# FlameClock_1_1_sh2.net
KiCad netlist of a schematic drawn in Altium Designer
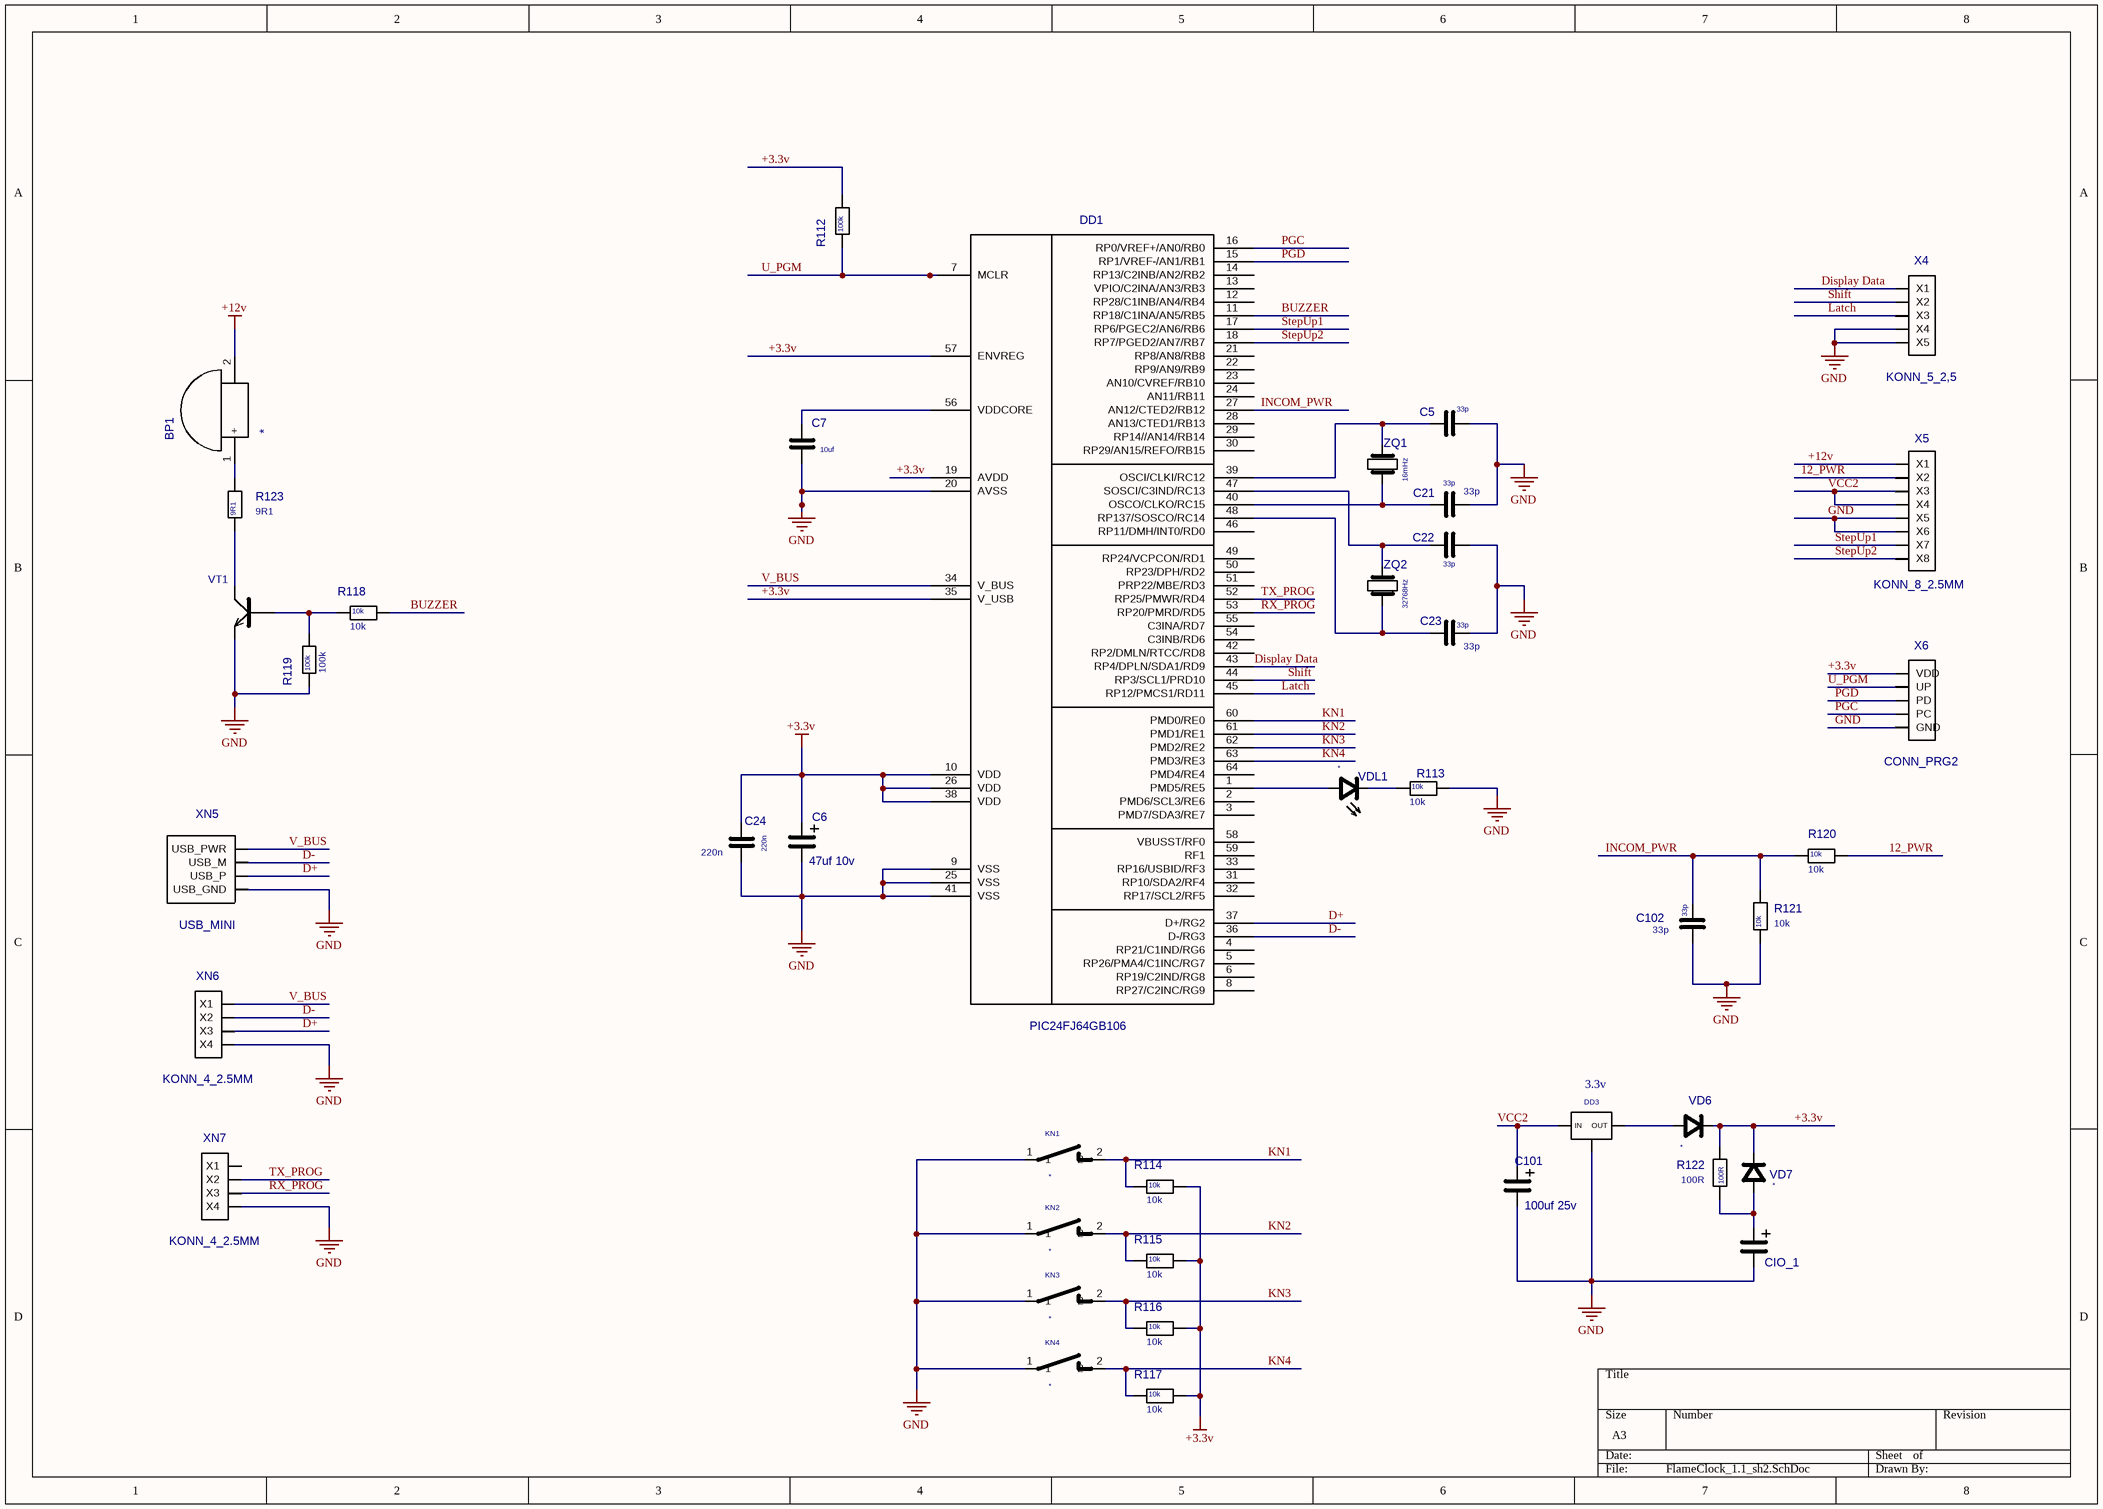
[diagram p0: FlameClock_1.1_sh2.SchDoc]

(export (version "E")
  (design (tool "Eeschema 10.0.6"))
  (components
    (comp (ref "BP1") (value "*") (footprint "ZIPPER") (libsource (lib "MyALib_Def") (part "Buzzer")))
    (comp (ref "C5") (value "33p") (footprint "CC0805_S") (libsource (lib "MyALib_Def") (part "C0805_S")))
    (comp (ref "C6")
      (value "47uf 10v")
      (footprint "CC0805_C_TANTAL_POLAR")
      (libsource (lib "MyALib_Def") (part "C0805_C_TAN_POLAR"))
    )
    (comp (ref "C7") (value "10uf") (footprint "CC0805_B") (libsource (lib "MyALib_Def") (part "C0805_B")))
    (comp (ref "C21")
      (value "33p")
      (footprint "CC0805_S")
      (fields (field (name "ALTIUM_VALUE") "33p"))
      (libsource (lib "MyALib_Def") (part "C0805_S"))
    )
    (comp (ref "C22") (value "33p") (footprint "CC0805_S") (libsource (lib "MyALib_Def") (part "C0805_S")))
    (comp (ref "C23")
      (value "33p")
      (footprint "CC0805_S")
      (fields (field (name "ALTIUM_VALUE") "33p"))
      (libsource (lib "MyALib_Def") (part "C0805_S"))
    )
    (comp (ref "C24")
      (value "220n")
      (footprint "CC0805_S")
      (fields (field (name "ALTIUM_VALUE") "220n"))
      (libsource (lib "my_lib_def") (part "C0805_S"))
    )
    (comp (ref "C101")
      (value "100uf 25v")
      (footprint "CE2.5")
      (libsource (lib "MyALib_Def") (part "CE2.5_5MM"))
    )
    (comp (ref "C102")
      (value "33p")
      (footprint "CC0805_S")
      (fields (field (name "ALTIUM_VALUE") "33p"))
      (libsource (lib "MyALib_Def") (part "C0805_S"))
    )
    (comp (ref "CIO_1") (value "*") (footprint "CE10") (libsource (lib "MyALib_Def") (part "CE5.0_10MM")))
    (comp (ref "DD1")
      (value "PIC24FJ64GB106")
      (footprint "TQFP-64")
      (libsource (lib "my_lib_mikroshem") (part "PIC24FJ64GB106"))
    )
    (comp (ref "DD3")
      (value "3.3v")
      (footprint "SOT223")
      (fields (field (name "Comment") "LD1117S"))
      (libsource (lib "MyALib_Microshem") (part "LD1117S"))
    )
    (comp (ref "KN1") (value "*") (footprint "KNOP_12X12") (libsource (lib "MyALib_Def") (part "KNOP_12X12")))
    (comp (ref "KN2") (value "*") (footprint "KNOP_12X12") (libsource (lib "MyALib_Def") (part "KNOP_12X12")))
    (comp (ref "KN3") (value "*") (footprint "KNOP_12X12") (libsource (lib "MyALib_Def") (part "KNOP_12X12")))
    (comp (ref "KN4") (value "*") (footprint "KNOP_12X12") (libsource (lib "MyALib_Def") (part "KNOP_12X12")))
    (comp (ref "R112") (value "100k") (footprint "R0805_S") (libsource (lib "MyALib_Def") (part "R0805_S")))
    (comp (ref "R113")
      (value "10k")
      (footprint "R0805_S")
      (fields (field (name "ALTIUM_VALUE") "10k"))
      (libsource (lib "MyALib_Def") (part "R0805_S"))
    )
    (comp (ref "R114")
      (value "10k")
      (footprint "R0805_S")
      (fields (field (name "ALTIUM_VALUE") "10k"))
      (libsource (lib "MyALib_Def") (part "R0805_S"))
    )
    (comp (ref "R115")
      (value "10k")
      (footprint "R0805_S")
      (fields (field (name "ALTIUM_VALUE") "10k"))
      (libsource (lib "MyALib_Def") (part "R0805_S"))
    )
    (comp (ref "R116")
      (value "10k")
      (footprint "R0805_S")
      (fields (field (name "ALTIUM_VALUE") "10k"))
      (libsource (lib "MyALib_Def") (part "R0805_S"))
    )
    (comp (ref "R117")
      (value "10k")
      (footprint "R0805_S")
      (fields (field (name "ALTIUM_VALUE") "10k"))
      (libsource (lib "MyALib_Def") (part "R0805_S"))
    )
    (comp (ref "R118")
      (value "10k")
      (footprint "R0805_S")
      (fields (field (name "ALTIUM_VALUE") "10k"))
      (libsource (lib "MyALib_Def") (part "R0805_S"))
    )
    (comp (ref "R119")
      (value "100k")
      (footprint "R0805_S")
      (fields (field (name "ALTIUM_VALUE") "100k"))
      (libsource (lib "MyALib_Def") (part "R0805_S"))
    )
    (comp (ref "R120")
      (value "10k")
      (footprint "R0805_S")
      (fields (field (name "ALTIUM_VALUE") "10k"))
      (libsource (lib "MyALib_Def") (part "R0805_S"))
    )
    (comp (ref "R121")
      (value "10k")
      (footprint "R0805_S")
      (fields (field (name "ALTIUM_VALUE") "10k"))
      (libsource (lib "MyALib_Def") (part "R0805_S"))
    )
    (comp (ref "R122")
      (value "100R")
      (footprint "R0805_S")
      (fields (field (name "ALTIUM_VALUE") "100R"))
      (libsource (lib "MyALib_Def") (part "R0805_S"))
    )
    (comp (ref "R123")
      (value "9R1")
      (footprint "R0805_S")
      (fields (field (name "ALTIUM_VALUE") "9R1"))
      (libsource (lib "MyALib_Def") (part "R0805_S"))
    )
    (comp (ref "VD6")
      (value "*")
      (footprint "DIOD_SOD123")
      (libsource (lib "MyALib_Def") (part "DIODE_SOD123"))
    )
    (comp (ref "VD7")
      (value "*")
      (footprint "DIOD_SOD123")
      (libsource (lib "MyALib_Def") (part "DIODE_SOD123"))
    )
    (comp (ref "VDL1") (value "*") (footprint "LED0805") (libsource (lib "MyALib_Def") (part "L_DIODE0805")))
    (comp (ref "VT1") (value "*") (footprint "SOT-23") (libsource (lib "MyALib_Def") (part "NPN_SOT23")))
    (comp (ref "X4")
      (value "KONN_5_2,5")
      (footprint "KONN_5_2.5MM")
      (libsource (lib "MyALib_Konnect") (part "KONN_5_2,5"))
    )
    (comp (ref "X5")
      (value "KONN_8_2.5MM")
      (footprint "KONN_8_2.5MM")
      (libsource (lib "MyALib_Konnect") (part "KONN_8_2.5MM"))
    )
    (comp (ref "X6")
      (value "CONN_PRG2")
      (footprint "CONN_PRG2")
      (libsource (lib "MyALib_Konnect") (part "CONN_PRG2"))
    )
    (comp (ref "XN5")
      (value "USB_MINI")
      (footprint "USB_MINI")
      (libsource (lib "MyALib_Konnect") (part "USB_MINI"))
    )
    (comp (ref "XN6")
      (value "KONN_4_2.5MM")
      (footprint "KONN_4_2.5MM")
      (libsource (lib "MyALib_Konnect") (part "KONN_4_2.5MM"))
    )
    (comp (ref "XN7")
      (value "KONN_4_2.5MM")
      (footprint "KONN_4_2.5MM")
      (libsource (lib "MyALib_Konnect") (part "KONN_4_2.5MM"))
    )
    (comp (ref "ZQ1") (value "16mHz") (footprint "ZQ") (libsource (lib "MyALib_Def") (part "ZQ")))
    (comp (ref "ZQ2")
      (value "32768Hz")
      (footprint "ZQ_CLOCK")
      (libsource (lib "MyALib_Def") (part "ZQ_CLOCK"))
    )
  )
  (nets
    (net (code "1") (name "+3.3v") (class "Default")
      (node (ref "C24") (pin "1") (pinfunction "1_1") (pintype "passive"))
      (node (ref "C6") (pin "2") (pinfunction "pl_2") (pintype "passive"))
      (node (ref "DD1") (pin "10") (pinfunction "VDD_10") (pintype "passive"))
      (node (ref "DD1") (pin "19") (pinfunction "AVDD_19") (pintype "passive"))
      (node (ref "DD1") (pin "26") (pinfunction "VDD_26") (pintype "passive"))
      (node (ref "DD1") (pin "35") (pinfunction "V_USB_35") (pintype "passive"))
      (node (ref "DD1") (pin "38") (pinfunction "VDD_38") (pintype "passive"))
      (node (ref "DD1") (pin "57") (pinfunction "ENVREG_57") (pintype "passive"))
      (node (ref "R112") (pin "1") (pinfunction "1_1") (pintype "passive"))
      (node (ref "R114") (pin "1") (pinfunction "1_1") (pintype "passive"))
      (node (ref "R115") (pin "1") (pinfunction "1_1") (pintype "passive"))
      (node (ref "R116") (pin "1") (pinfunction "1_1") (pintype "passive"))
      (node (ref "R117") (pin "1") (pinfunction "1_1") (pintype "passive"))
      (node (ref "R122") (pin "1") (pinfunction "1_1") (pintype "passive"))
      (node (ref "VD6") (pin "1") (pinfunction "k_1") (pintype "passive"))
      (node (ref "VD7") (pin "1") (pinfunction "k_1") (pintype "passive"))
      (node (ref "X6") (pin "1") (pinfunction "VDD_1") (pintype "passive"))
    )
    (net (code "2") (name "+12v") (class "Default")
      (node (ref "BP1") (pin "2") (pinfunction "-_2") (pintype "passive"))
      (node (ref "X5") (pin "1") (pinfunction "X1_1") (pintype "passive"))
    )
    (net (code "3") (name "/12_PWR") (class "Default")
      (node (ref "R120") (pin "1") (pinfunction "1_1") (pintype "passive"))
      (node (ref "X5") (pin "2") (pinfunction "X2_2") (pintype "passive"))
    )
    (net (code "4") (name "/BUZZER") (class "Default")
      (node (ref "DD1") (pin "11") (pinfunction "RP18/C1INA/AN5/RB5_11") (pintype "passive"))
      (node (ref "R118") (pin "1") (pinfunction "1_1") (pintype "passive"))
    )
    (net (code "5") (name "/D+") (class "Default")
      (node (ref "DD1") (pin "37") (pinfunction "D+/RG2_37") (pintype "passive"))
      (node (ref "XN5") (pin "3") (pinfunction "USB_P_3") (pintype "passive"))
      (node (ref "XN6") (pin "3") (pinfunction "X3_3") (pintype "passive"))
    )
    (net (code "6") (name "/D-") (class "Default")
      (node (ref "DD1") (pin "36") (pinfunction "D-/RG3_36") (pintype "passive"))
      (node (ref "XN5") (pin "2") (pinfunction "USB_M_2") (pintype "passive"))
      (node (ref "XN6") (pin "2") (pinfunction "X2_2") (pintype "passive"))
    )
    (net (code "7") (name "/Display Data") (class "Default")
      (node (ref "DD1") (pin "43") (pinfunction "RP4/DPLN/SDA1/RD9_43") (pintype "passive"))
      (node (ref "X4") (pin "1") (pinfunction "X1_1") (pintype "passive"))
    )
    (net (code "8") (name "/INCOM_PWR") (class "Default")
      (node (ref "C102") (pin "2") (pinfunction "2_2") (pintype "passive"))
      (node (ref "DD1") (pin "27") (pinfunction "AN12/CTED2/RB12_27") (pintype "passive"))
      (node (ref "R120") (pin "2") (pinfunction "2_2") (pintype "passive"))
      (node (ref "R121") (pin "1") (pinfunction "1_1") (pintype "passive"))
    )
    (net (code "9") (name "/KN1") (class "Default")
      (node (ref "DD1") (pin "60") (pinfunction "PMD0/RE0_60") (pintype "passive"))
      (node (ref "KN1") (pin "2") (pinfunction "2_2") (pintype "passive"))
      (node (ref "R114") (pin "2") (pinfunction "2_2") (pintype "passive"))
    )
    (net (code "10") (name "/KN2") (class "Default")
      (node (ref "DD1") (pin "61") (pinfunction "PMD1/RE1_61") (pintype "passive"))
      (node (ref "KN2") (pin "2") (pinfunction "2_2") (pintype "passive"))
      (node (ref "R115") (pin "2") (pinfunction "2_2") (pintype "passive"))
    )
    (net (code "11") (name "/KN3") (class "Default")
      (node (ref "DD1") (pin "62") (pinfunction "PMD2/RE2_62") (pintype "passive"))
      (node (ref "KN3") (pin "2") (pinfunction "2_2") (pintype "passive"))
      (node (ref "R116") (pin "2") (pinfunction "2_2") (pintype "passive"))
    )
    (net (code "12") (name "/KN4") (class "Default")
      (node (ref "DD1") (pin "63") (pinfunction "PMD3/RE3_63") (pintype "passive"))
      (node (ref "KN4") (pin "2") (pinfunction "2_2") (pintype "passive"))
      (node (ref "R117") (pin "2") (pinfunction "2_2") (pintype "passive"))
    )
    (net (code "13") (name "/Latch") (class "Default")
      (node (ref "DD1") (pin "45") (pinfunction "RP12/PMCS1/RD11_45") (pintype "passive"))
      (node (ref "X4") (pin "3") (pinfunction "X3_3") (pintype "passive"))
    )
    (net (code "14") (name "/PGC") (class "Default")
      (node (ref "DD1") (pin "16") (pinfunction "RP0/VREF+/AN0/RB0_16") (pintype "passive"))
      (node (ref "X6") (pin "4") (pinfunction "PC_4") (pintype "passive"))
    )
    (net (code "15") (name "/PGD") (class "Default")
      (node (ref "DD1") (pin "15") (pinfunction "RP1/VREF-/AN1/RB1_15") (pintype "passive"))
      (node (ref "X6") (pin "3") (pinfunction "PD_3") (pintype "passive"))
    )
    (net (code "16") (name "/RX_PROG") (class "Default")
      (node (ref "DD1") (pin "53") (pinfunction "RP20/PMRD/RD5_53") (pintype "passive"))
      (node (ref "XN7") (pin "3") (pinfunction "X3_3") (pintype "passive"))
    )
    (net (code "17") (name "/Shift") (class "Default")
      (node (ref "DD1") (pin "44") (pinfunction "RP3/SCL1/PRD10_44") (pintype "passive"))
      (node (ref "X4") (pin "2") (pinfunction "X2_2") (pintype "passive"))
    )
    (net (code "18") (name "/StepUp1") (class "Default")
      (node (ref "DD1") (pin "17") (pinfunction "RP6/PGEC2/AN6/RB6_17") (pintype "passive"))
      (node (ref "X5") (pin "7") (pinfunction "X7_7") (pintype "passive"))
    )
    (net (code "19") (name "/StepUp2") (class "Default")
      (node (ref "DD1") (pin "18") (pinfunction "RP7/PGED2/AN7/RB7_18") (pintype "passive"))
      (node (ref "X5") (pin "8") (pinfunction "X8_8") (pintype "passive"))
    )
    (net (code "20") (name "/TX_PROG") (class "Default")
      (node (ref "DD1") (pin "52") (pinfunction "RP25/PMWR/RD4_52") (pintype "passive"))
      (node (ref "XN7") (pin "2") (pinfunction "X2_2") (pintype "passive"))
    )
    (net (code "21") (name "/U_PGM") (class "Default")
      (node (ref "DD1") (pin "7") (pinfunction "MCLR_7") (pintype "passive"))
      (node (ref "R112") (pin "2") (pinfunction "2_2") (pintype "passive"))
      (node (ref "X6") (pin "2") (pinfunction "UP_2") (pintype "passive"))
    )
    (net (code "22") (name "/VCC2") (class "Default")
      (node (ref "C101") (pin "1") (pinfunction "1_1") (pintype "passive"))
      (node (ref "DD3") (pin "1") (pinfunction "IN_1") (pintype "passive"))
      (node (ref "X5") (pin "3") (pinfunction "X3_3") (pintype "passive"))
      (node (ref "X5") (pin "4") (pinfunction "X4_4") (pintype "passive"))
    )
    (net (code "23") (name "/V_BUS") (class "Default")
      (node (ref "DD1") (pin "34") (pinfunction "V_BUS_34") (pintype "passive"))
      (node (ref "XN5") (pin "1") (pinfunction "USB_PWR_1") (pintype "passive"))
      (node (ref "XN6") (pin "1") (pinfunction "X1_1") (pintype "passive"))
    )
    (net (code "24") (name "GND") (class "Default")
      (node (ref "C101") (pin "2") (pinfunction "2_2") (pintype "passive"))
      (node (ref "C102") (pin "1") (pinfunction "1_1") (pintype "passive"))
      (node (ref "C21") (pin "2") (pinfunction "2_2") (pintype "passive"))
      (node (ref "C22") (pin "2") (pinfunction "2_2") (pintype "passive"))
      (node (ref "C23") (pin "2") (pinfunction "2_2") (pintype "passive"))
      (node (ref "C24") (pin "2") (pinfunction "2_2") (pintype "passive"))
      (node (ref "C5") (pin "2") (pinfunction "2_2") (pintype "passive"))
      (node (ref "C6") (pin "1") (pinfunction "min_1") (pintype "passive"))
      (node (ref "C7") (pin "2") (pinfunction "2_2") (pintype "passive"))
      (node (ref "CIO_1") (pin "2") (pinfunction "min_2") (pintype "passive"))
      (node (ref "DD1") (pin "20") (pinfunction "AVSS_20") (pintype "passive"))
      (node (ref "DD1") (pin "25") (pinfunction "VSS_25") (pintype "passive"))
      (node (ref "DD1") (pin "41") (pinfunction "VSS_41") (pintype "passive"))
      (node (ref "DD1") (pin "9") (pinfunction "VSS_9") (pintype "passive"))
      (node (ref "DD3") (pin "3") (pinfunction "GND_3") (pintype "passive"))
      (node (ref "KN1") (pin "1") (pinfunction "1_1") (pintype "passive"))
      (node (ref "KN2") (pin "1") (pinfunction "1_1") (pintype "passive"))
      (node (ref "KN3") (pin "1") (pinfunction "1_1") (pintype "passive"))
      (node (ref "KN4") (pin "1") (pinfunction "1_1") (pintype "passive"))
      (node (ref "R113") (pin "1") (pinfunction "1_1") (pintype "passive"))
      (node (ref "R119") (pin "2") (pinfunction "2_2") (pintype "passive"))
      (node (ref "R121") (pin "2") (pinfunction "2_2") (pintype "passive"))
      (node (ref "VT1") (pin "3") (pinfunction "e_3") (pintype "passive"))
      (node (ref "X4") (pin "4") (pinfunction "X4_4") (pintype "passive"))
      (node (ref "X4") (pin "5") (pinfunction "X5_5") (pintype "passive"))
      (node (ref "X5") (pin "5") (pinfunction "X5_5") (pintype "passive"))
      (node (ref "X5") (pin "6") (pinfunction "X6_6") (pintype "passive"))
      (node (ref "X6") (pin "5") (pinfunction "GND_5") (pintype "passive"))
      (node (ref "XN5") (pin "5") (pinfunction "USB_GND_5") (pintype "passive"))
      (node (ref "XN6") (pin "4") (pinfunction "X4_4") (pintype "passive"))
      (node (ref "XN7") (pin "4") (pinfunction "X4_4") (pintype "passive"))
    )
    (net (code "25") (name "Net-(BP1-+)") (class "Default")
      (node (ref "BP1") (pin "1") (pinfunction "+_1") (pintype "passive"))
      (node (ref "R123") (pin "1") (pinfunction "1_1") (pintype "passive"))
    )
    (net (code "26") (name "Net-(CIO_1-pl)") (class "Default")
      (node (ref "CIO_1") (pin "1") (pinfunction "pl_1") (pintype "passive"))
      (node (ref "R122") (pin "2") (pinfunction "2_2") (pintype "passive"))
      (node (ref "VD7") (pin "2") (pinfunction "a_2") (pintype "passive"))
    )
    (net (code "27") (name "Net-(DD1-OSCI{slash}CLKI{slash}RC12)") (class "Default")
      (node (ref "C5") (pin "1") (pinfunction "1_1") (pintype "passive"))
      (node (ref "DD1") (pin "39") (pinfunction "OSCI/CLKI/RC12_39") (pintype "passive"))
      (node (ref "ZQ1") (pin "1") (pinfunction "1_1") (pintype "passive"))
    )
    (net (code "28") (name "Net-(DD1-OSCO{slash}CLKO{slash}RC15)") (class "Default")
      (node (ref "C21") (pin "1") (pinfunction "1_1") (pintype "passive"))
      (node (ref "DD1") (pin "40") (pinfunction "OSCO/CLKO/RC15_40") (pintype "passive"))
      (node (ref "ZQ1") (pin "2") (pinfunction "2_2") (pintype "passive"))
    )
    (net (code "29") (name "Net-(DD1-PMD5{slash}RE5)") (class "Default")
      (node (ref "DD1") (pin "1") (pinfunction "PMD5/RE5_1") (pintype "passive"))
      (node (ref "VDL1") (pin "2") (pinfunction "2_2") (pintype "passive"))
    )
    (net (code "30") (name "Net-(DD1-RP137{slash}SOSCO{slash}RC14)") (class "Default")
      (node (ref "C23") (pin "1") (pinfunction "1_1") (pintype "passive"))
      (node (ref "DD1") (pin "48") (pinfunction "RP137/SOSCO/RC14_48") (pintype "passive"))
      (node (ref "ZQ2") (pin "2") (pinfunction "2_2") (pintype "passive"))
    )
    (net (code "31") (name "Net-(DD1-SOSCI{slash}C3IND{slash}RC13)") (class "Default")
      (node (ref "C22") (pin "1") (pinfunction "1_1") (pintype "passive"))
      (node (ref "DD1") (pin "47") (pinfunction "SOSCI/C3IND/RC13_47") (pintype "passive"))
      (node (ref "ZQ2") (pin "1") (pinfunction "1_1") (pintype "passive"))
    )
    (net (code "32") (name "Net-(DD1-VDDCORE)") (class "Default")
      (node (ref "C7") (pin "1") (pinfunction "1_1") (pintype "passive"))
      (node (ref "DD1") (pin "56") (pinfunction "VDDCORE_56") (pintype "passive"))
    )
    (net (code "33") (name "Net-(DD3-OUT)") (class "Default")
      (node (ref "DD3") (pin "2") (pinfunction "OUT_2") (pintype "passive"))
      (node (ref "VD6") (pin "2") (pinfunction "a_2") (pintype "passive"))
    )
    (net (code "34") (name "Net-(R113-Pad2)") (class "Default")
      (node (ref "R113") (pin "2") (pinfunction "2_2") (pintype "passive"))
      (node (ref "VDL1") (pin "1") (pinfunction "1_1") (pintype "passive"))
    )
    (net (code "35") (name "Net-(VT1-b)") (class "Default")
      (node (ref "R118") (pin "2") (pinfunction "2_2") (pintype "passive"))
      (node (ref "R119") (pin "1") (pinfunction "1_1") (pintype "passive"))
      (node (ref "VT1") (pin "1") (pinfunction "b_1") (pintype "passive"))
    )
    (net (code "36") (name "Net-(VT1-k)") (class "Default")
      (node (ref "R123") (pin "2") (pinfunction "2_2") (pintype "passive"))
      (node (ref "VT1") (pin "2") (pinfunction "k_2") (pintype "passive"))
    )
    (net (code "37") (name "unconnected-(DD1-AN10{slash}CVREF{slash}RB10-Pad23)") (class "Default")
      (node (ref "DD1") (pin "23") (pinfunction "AN10/CVREF/RB10_23") (pintype "passive"))
    )
    (net (code "38") (name "unconnected-(DD1-AN11{slash}RB11-Pad24)") (class "Default")
      (node (ref "DD1") (pin "24") (pinfunction "AN11/RB11_24") (pintype "passive"))
    )
    (net (code "39") (name "unconnected-(DD1-AN13{slash}CTED1{slash}RB13-Pad28)") (class "Default")
      (node (ref "DD1") (pin "28") (pinfunction "AN13/CTED1/RB13_28") (pintype "passive"))
    )
    (net (code "40") (name "unconnected-(DD1-C3INA{slash}RD7-Pad55)") (class "Default")
      (node (ref "DD1") (pin "55") (pinfunction "C3INA/RD7_55") (pintype "passive"))
    )
    (net (code "41") (name "unconnected-(DD1-C3INB{slash}RD6-Pad54)") (class "Default")
      (node (ref "DD1") (pin "54") (pinfunction "C3INB/RD6_54") (pintype "passive"))
    )
    (net (code "42") (name "unconnected-(DD1-PMD4{slash}RE4-Pad64)") (class "Default")
      (node (ref "DD1") (pin "64") (pinfunction "PMD4/RE4_64") (pintype "passive"))
    )
    (net (code "43") (name "unconnected-(DD1-PMD6{slash}SCL3{slash}RE6-Pad2)") (class "Default")
      (node (ref "DD1") (pin "2") (pinfunction "PMD6/SCL3/RE6_2") (pintype "passive"))
    )
    (net (code "44") (name "unconnected-(DD1-PMD7{slash}SDA3{slash}RE7-Pad3)") (class "Default")
      (node (ref "DD1") (pin "3") (pinfunction "PMD7/SDA3/RE7_3") (pintype "passive"))
    )
    (net (code "45") (name "unconnected-(DD1-PRP22{slash}MBE{slash}RD3-Pad51)") (class "Default")
      (node (ref "DD1") (pin "51") (pinfunction "PRP22/MBE/RD3_51") (pintype "passive"))
    )
    (net (code "46") (name "unconnected-(DD1-RF1-Pad59)") (class "Default")
      (node (ref "DD1") (pin "59") (pinfunction "RF1_59") (pintype "passive"))
    )
    (net (code "47") (name "unconnected-(DD1-RP2{slash}DMLN{slash}RTCC{slash}RD8-Pad42)") (class "Default")
      (node (ref "DD1") (pin "42") (pinfunction "RP2/DMLN/RTCC/RD8_42") (pintype "passive"))
    )
    (net (code "48") (name "unconnected-(DD1-RP8{slash}AN8{slash}RB8-Pad21)") (class "Default")
      (node (ref "DD1") (pin "21") (pinfunction "RP8/AN8/RB8_21") (pintype "passive"))
    )
    (net (code "49") (name "unconnected-(DD1-RP9{slash}AN9{slash}RB9-Pad22)") (class "Default")
      (node (ref "DD1") (pin "22") (pinfunction "RP9/AN9/RB9_22") (pintype "passive"))
    )
    (net (code "50") (name "unconnected-(DD1-RP10{slash}SDA2{slash}RF4-Pad31)") (class "Default")
      (node (ref "DD1") (pin "31") (pinfunction "RP10/SDA2/RF4_31") (pintype "passive"))
    )
    (net (code "51") (name "unconnected-(DD1-RP11{slash}DMH{slash}INT0{slash}RD0-Pad46)") (class "Default")
      (node (ref "DD1") (pin "46") (pinfunction "RP11/DMH/INT0/RD0_46") (pintype "passive"))
    )
    (net (code "52") (name "unconnected-(DD1-RP13{slash}C2INB{slash}AN2{slash}RB2-Pad14)") (class "Default")
      (node (ref "DD1") (pin "14") (pinfunction "RP13/C2INB/AN2/RB2_14") (pintype "passive"))
    )
    (net (code "53") (name "unconnected-(DD1-RP14{slash}{slash}AN14{slash}RB14-Pad29)") (class "Default")
      (node (ref "DD1") (pin "29") (pinfunction "RP14//AN14/RB14_29") (pintype "passive"))
    )
    (net (code "54") (name "unconnected-(DD1-RP16{slash}USBID{slash}RF3-Pad33)") (class "Default")
      (node (ref "DD1") (pin "33") (pinfunction "RP16/USBID/RF3_33") (pintype "passive"))
    )
    (net (code "55") (name "unconnected-(DD1-RP17{slash}SCL2{slash}RF5-Pad32)") (class "Default")
      (node (ref "DD1") (pin "32") (pinfunction "RP17/SCL2/RF5_32") (pintype "passive"))
    )
    (net (code "56") (name "unconnected-(DD1-RP19{slash}C2IND{slash}RG8-Pad6)") (class "Default")
      (node (ref "DD1") (pin "6") (pinfunction "RP19/C2IND/RG8_6") (pintype "passive"))
    )
    (net (code "57") (name "unconnected-(DD1-RP21{slash}C1IND{slash}RG6-Pad4)") (class "Default")
      (node (ref "DD1") (pin "4") (pinfunction "RP21/C1IND/RG6_4") (pintype "passive"))
    )
    (net (code "58") (name "unconnected-(DD1-RP23{slash}DPH{slash}RD2-Pad50)") (class "Default")
      (node (ref "DD1") (pin "50") (pinfunction "RP23/DPH/RD2_50") (pintype "passive"))
    )
    (net (code "59") (name "unconnected-(DD1-RP24{slash}VCPCON{slash}RD1-Pad49)") (class "Default")
      (node (ref "DD1") (pin "49") (pinfunction "RP24/VCPCON/RD1_49") (pintype "passive"))
    )
    (net (code "60") (name "unconnected-(DD1-RP26{slash}PMA4{slash}C1INC{slash}RG7-Pad5)") (class "Default")
      (node (ref "DD1") (pin "5") (pinfunction "RP26/PMA4/C1INC/RG7_5") (pintype "passive"))
    )
    (net (code "61") (name "unconnected-(DD1-RP27{slash}C2INC{slash}RG9-Pad8)") (class "Default")
      (node (ref "DD1") (pin "8") (pinfunction "RP27/C2INC/RG9_8") (pintype "passive"))
    )
    (net (code "62") (name "unconnected-(DD1-RP28{slash}C1INB{slash}AN4{slash}RB4-Pad12)") (class "Default")
      (node (ref "DD1") (pin "12") (pinfunction "RP28/C1INB/AN4/RB4_12") (pintype "passive"))
    )
    (net (code "63") (name "unconnected-(DD1-RP29{slash}AN15{slash}REFO{slash}RB15-Pad30)") (class "Default")
      (node (ref "DD1") (pin "30") (pinfunction "RP29/AN15/REFO/RB15_30") (pintype "passive"))
    )
    (net (code "64") (name "unconnected-(DD1-VBUSST{slash}RF0-Pad58)") (class "Default")
      (node (ref "DD1") (pin "58") (pinfunction "VBUSST/RF0_58") (pintype "passive"))
    )
    (net (code "65") (name "unconnected-(DD1-VPIO{slash}C2INA{slash}AN3{slash}RB3-Pad13)") (class "Default")
      (node (ref "DD1") (pin "13") (pinfunction "VPIO/C2INA/AN3/RB3_13") (pintype "passive"))
    )
    (net (code "66") (name "unconnected-(DD3-Pad4)") (class "Default")
      (node (ref "DD3") (pin "4") (pintype "passive"))
    )
    (net (code "67") (name "unconnected-(KN1-Pad3)") (class "Default")
      (node (ref "KN1") (pin "3") (pintype "passive"))
    )
    (net (code "68") (name "unconnected-(KN1-Pad4)") (class "Default")
      (node (ref "KN1") (pin "4") (pintype "passive"))
    )
    (net (code "69") (name "unconnected-(KN2-Pad3)") (class "Default")
      (node (ref "KN2") (pin "3") (pintype "passive"))
    )
    (net (code "70") (name "unconnected-(KN2-Pad4)") (class "Default")
      (node (ref "KN2") (pin "4") (pintype "passive"))
    )
    (net (code "71") (name "unconnected-(KN3-Pad3)") (class "Default")
      (node (ref "KN3") (pin "3") (pintype "passive"))
    )
    (net (code "72") (name "unconnected-(KN3-Pad4)") (class "Default")
      (node (ref "KN3") (pin "4") (pintype "passive"))
    )
    (net (code "73") (name "unconnected-(KN4-Pad3)") (class "Default")
      (node (ref "KN4") (pin "3") (pintype "passive"))
    )
    (net (code "74") (name "unconnected-(KN4-Pad4)") (class "Default")
      (node (ref "KN4") (pin "4") (pintype "passive"))
    )
    (net (code "75") (name "unconnected-(XN5-Pad4)") (class "Default")
      (node (ref "XN5") (pin "4") (pintype "passive"))
    )
    (net (code "76") (name "unconnected-(XN5-Pad6)") (class "Default")
      (node (ref "XN5") (pin "6") (pintype "passive"))
    )
    (net (code "77") (name "unconnected-(XN5-Pad7)") (class "Default")
      (node (ref "XN5") (pin "7") (pintype "passive"))
    )
    (net (code "78") (name "unconnected-(XN5-Pad8)") (class "Default")
      (node (ref "XN5") (pin "8") (pintype "passive"))
    )
    (net (code "79") (name "unconnected-(XN5-Pad9)") (class "Default")
      (node (ref "XN5") (pin "9") (pintype "passive"))
    )
    (net (code "80") (name "unconnected-(XN7-X1-Pad1)") (class "Default")
      (node (ref "XN7") (pin "1") (pinfunction "X1_1") (pintype "passive"))
    )
    (net (code "81") (name "unconnected-(ZQ2-Pad3)") (class "Default")
      (node (ref "ZQ2") (pin "3") (pintype "passive"))
    )
  )
)
